# Oscar_s_schematic.net
KiCad netlist of a schematic drawn in EAGLE
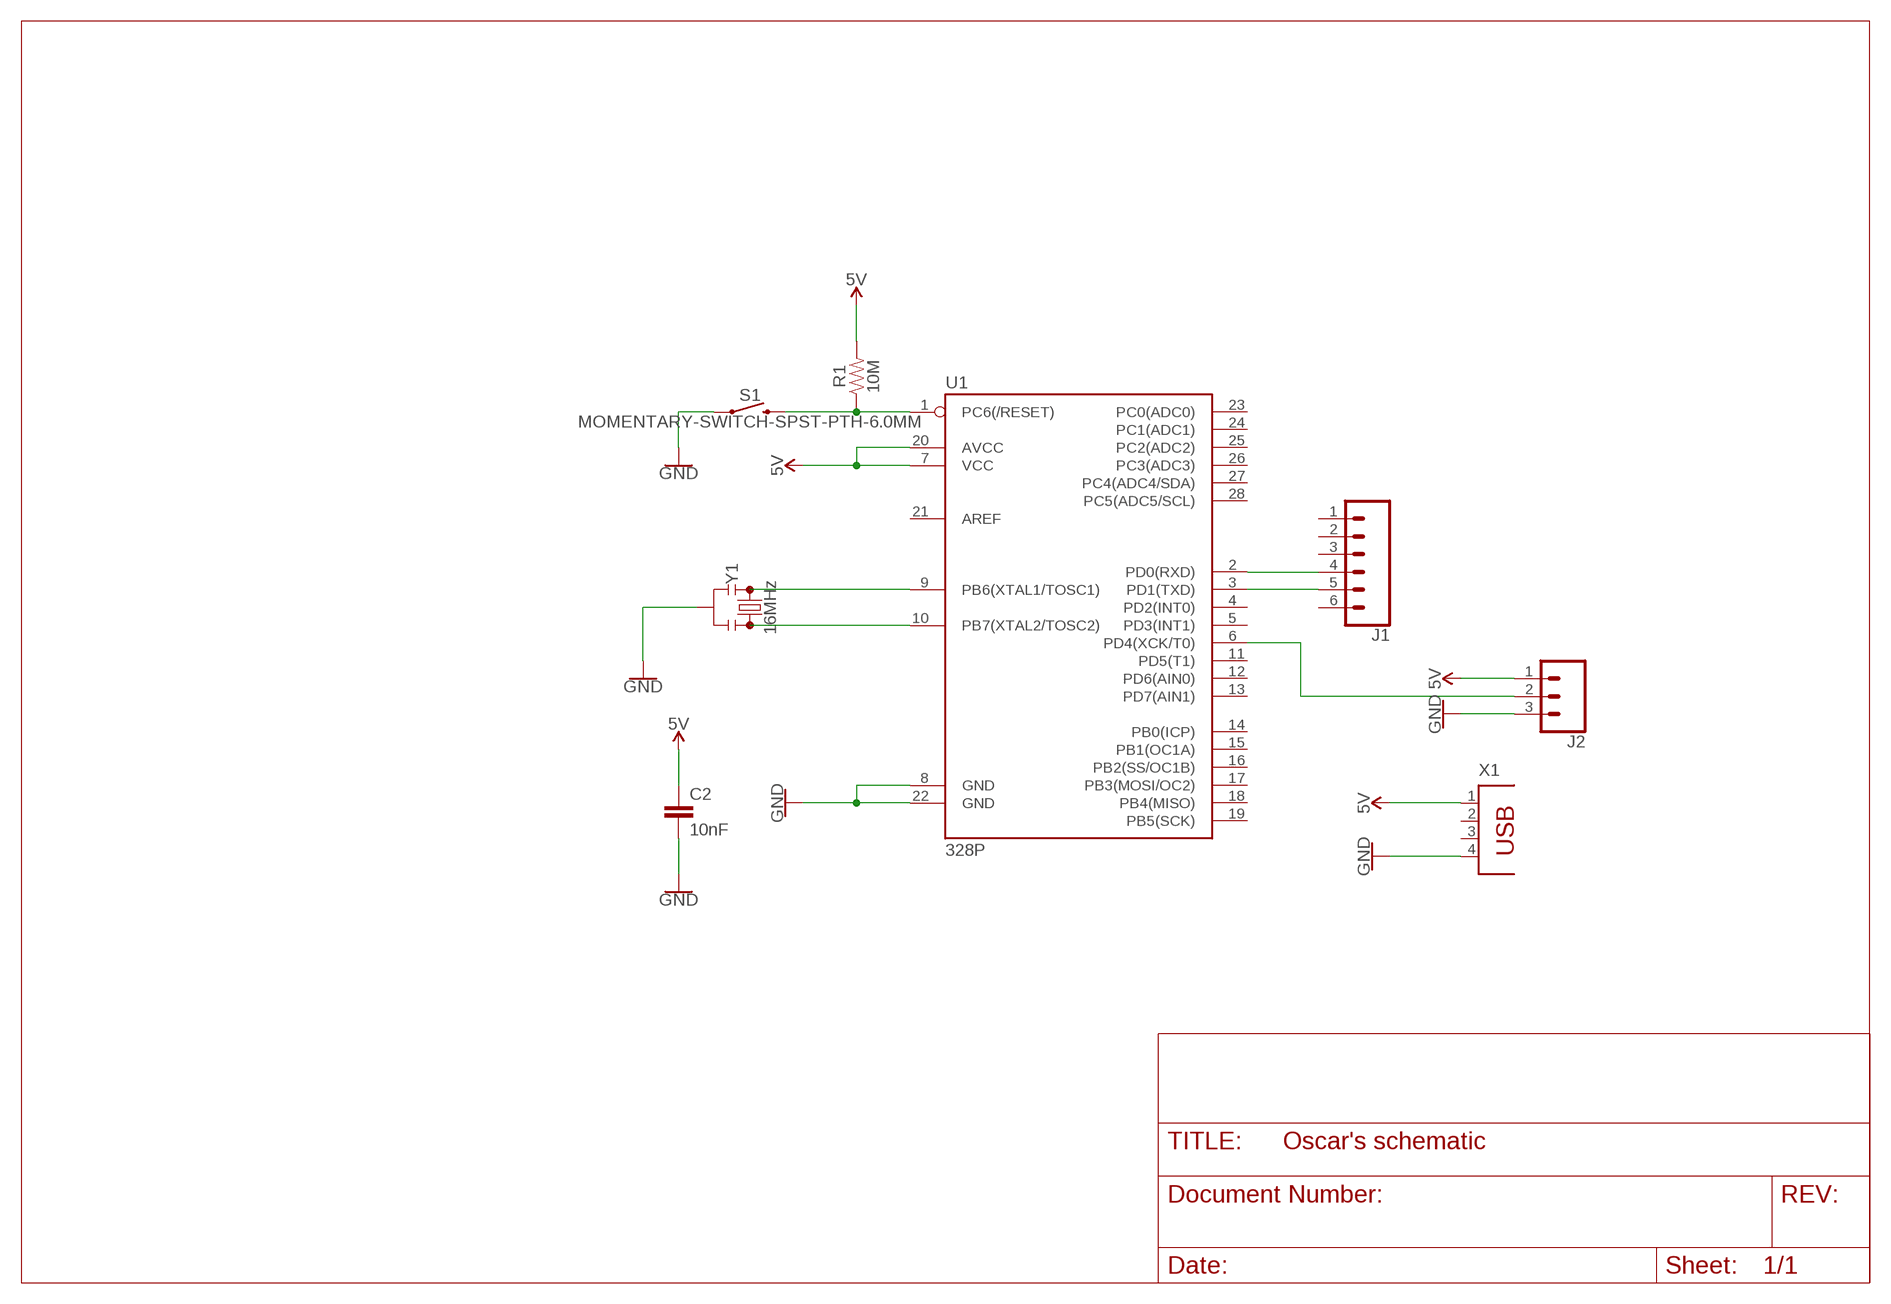
[diagram p0: schematic, sheet 1]

(export (version "E")
  (design (tool "Eeschema 10.0.6"))
  (components
    (comp (ref "C2")
      (value "10nF")
      (footprint "eagle-import:CAP-PTH-10MM")
      (libsource (lib "eagle-import") (part "10NF-PTH-10MM-10000V-1-%"))
    )
    (comp (ref "J1")
      (value "CONN_06LOCK")
      (footprint "eagle-import:1X06_LOCK")
      (libsource (lib "eagle-import") (part "CONN_06LOCK"))
    )
    (comp (ref "J2")
      (value "CONN_03")
      (footprint "eagle-import:1X03")
      (libsource (lib "eagle-import") (part "CONN_03"))
    )
    (comp (ref "R1")
      (value "10M")
      (footprint "eagle-import:AXIAL-0.3")
      (libsource (lib "eagle-import") (part "10MOHM-HORIZ-1/4W-5%"))
    )
    (comp (ref "S1")
      (value "MOMENTARY-SWITCH-SPST-PTH-6.0MM")
      (footprint "eagle-import:TACTILE_SWITCH_PTH_6.0MM")
      (libsource (lib "eagle-import") (part "MOMENTARY-SWITCH-SPST-PTH-6.0MM"))
    )
    (comp (ref "U1")
      (value "328P")
      (footprint "eagle-import:DIP28")
      (libsource (lib "eagle-import") (part "ATMEGA328P_PDIP"))
    )
    (comp (ref "X1")
      (value "PN61729")
      (footprint "eagle-import:PN61729")
      (libsource (lib "eagle-import") (part "PN61729"))
    )
    (comp (ref "Y1")
      (value "16MHz")
      (footprint "eagle-import:RESONATOR-SMD-3.2X1.3")
      (libsource (lib "eagle-import") (part "RESONATOR-16MHZSMD_3.2X1.3"))
    )
  )
  (nets
    (net (code "1") (name "5V") (class "Default")
      (node (ref "C2") (pin "1") (pinfunction "1_1") (pintype "passive"))
      (node (ref "J2") (pin "1") (pinfunction "1_1") (pintype "passive"))
      (node (ref "R1") (pin "P$2") (pinfunction "2_P$2") (pintype "passive"))
      (node (ref "U1") (pin "20") (pinfunction "AVCC_20") (pintype "bidirectional"))
      (node (ref "U1") (pin "7") (pinfunction "VCC_7") (pintype "bidirectional"))
      (node (ref "X1") (pin "1") (pinfunction "1_1") (pintype "passive"))
    )
    (net (code "2") (name "GND") (class "Default")
      (node (ref "C2") (pin "2") (pinfunction "2_2") (pintype "passive"))
      (node (ref "J2") (pin "3") (pinfunction "3_3") (pintype "passive"))
      (node (ref "S1") (pin "1") (pinfunction "1_1") (pintype "passive"))
      (node (ref "U1") (pin "22") (pinfunction "GND_22") (pintype "bidirectional"))
      (node (ref "U1") (pin "8") (pinfunction "GND_8") (pintype "bidirectional"))
      (node (ref "X1") (pin "4") (pinfunction "4_4") (pintype "passive"))
      (node (ref "Y1") (pin "2") (pinfunction "2_2") (pintype "passive"))
    )
    (net (code "3") (name "Net-(R1-1)") (class "Default")
      (node (ref "R1") (pin "P$1") (pinfunction "1_P$1") (pintype "passive"))
      (node (ref "S1") (pin "3") (pinfunction "2_3") (pintype "passive"))
      (node (ref "U1") (pin "1") (pinfunction "PC6(/RESET)_1") (pintype "bidirectional"))
    )
    (net (code "4") (name "Net-(U1-PB6(XTAL1{slash}TOSC1))") (class "Default")
      (node (ref "U1") (pin "9") (pinfunction "PB6(XTAL1/TOSC1)_9") (pintype "bidirectional"))
      (node (ref "Y1") (pin "1") (pinfunction "1_1") (pintype "passive"))
    )
    (net (code "5") (name "Net-(U1-PB7(XTAL2{slash}TOSC2))") (class "Default")
      (node (ref "U1") (pin "10") (pinfunction "PB7(XTAL2/TOSC2)_10") (pintype "bidirectional"))
      (node (ref "Y1") (pin "3") (pinfunction "3_3") (pintype "passive"))
    )
    (net (code "6") (name "Net-(U1-PD0(RXD))") (class "Default")
      (node (ref "J1") (pin "4") (pinfunction "4_4") (pintype "passive"))
      (node (ref "U1") (pin "2") (pinfunction "PD0(RXD)_2") (pintype "bidirectional"))
    )
    (net (code "7") (name "Net-(U1-PD1(TXD))") (class "Default")
      (node (ref "J1") (pin "5") (pinfunction "5_5") (pintype "passive"))
      (node (ref "U1") (pin "3") (pinfunction "PD1(TXD)_3") (pintype "bidirectional"))
    )
    (net (code "8") (name "Net-(U1-PD4(XCK{slash}T0))") (class "Default")
      (node (ref "J2") (pin "2") (pinfunction "2_2") (pintype "passive"))
      (node (ref "U1") (pin "6") (pinfunction "PD4(XCK/T0)_6") (pintype "bidirectional"))
    )
    (net (code "9") (name "unconnected-(J1-Pad1)") (class "Default")
      (node (ref "J1") (pin "1") (pinfunction "1_1") (pintype "passive"))
    )
    (net (code "10") (name "unconnected-(J1-Pad2)") (class "Default")
      (node (ref "J1") (pin "2") (pinfunction "2_2") (pintype "passive"))
    )
    (net (code "11") (name "unconnected-(J1-Pad3)") (class "Default")
      (node (ref "J1") (pin "3") (pinfunction "3_3") (pintype "passive"))
    )
    (net (code "12") (name "unconnected-(J1-Pad6)") (class "Default")
      (node (ref "J1") (pin "6") (pinfunction "6_6") (pintype "passive"))
    )
    (net (code "13") (name "unconnected-(U1-AREF-Pad21)") (class "Default")
      (node (ref "U1") (pin "21") (pinfunction "AREF_21") (pintype "bidirectional"))
    )
    (net (code "14") (name "unconnected-(U1-PB0(ICP)-Pad14)") (class "Default")
      (node (ref "U1") (pin "14") (pinfunction "PB0(ICP)_14") (pintype "bidirectional"))
    )
    (net (code "15") (name "unconnected-(U1-PB1(OC1A)-Pad15)") (class "Default")
      (node (ref "U1") (pin "15") (pinfunction "PB1(OC1A)_15") (pintype "bidirectional"))
    )
    (net (code "16") (name "unconnected-(U1-PB2(SS{slash}OC1B)-Pad16)") (class "Default")
      (node (ref "U1") (pin "16") (pinfunction "PB2(SS/OC1B)_16") (pintype "bidirectional"))
    )
    (net (code "17") (name "unconnected-(U1-PB3(MOSI{slash}OC2)-Pad17)") (class "Default")
      (node (ref "U1") (pin "17") (pinfunction "PB3(MOSI/OC2)_17") (pintype "bidirectional"))
    )
    (net (code "18") (name "unconnected-(U1-PB4(MISO)-Pad18)") (class "Default")
      (node (ref "U1") (pin "18") (pinfunction "PB4(MISO)_18") (pintype "bidirectional"))
    )
    (net (code "19") (name "unconnected-(U1-PB5(SCK)-Pad19)") (class "Default")
      (node (ref "U1") (pin "19") (pinfunction "PB5(SCK)_19") (pintype "bidirectional"))
    )
    (net (code "20") (name "unconnected-(U1-PC0(ADC0)-Pad23)") (class "Default")
      (node (ref "U1") (pin "23") (pinfunction "PC0(ADC0)_23") (pintype "bidirectional"))
    )
    (net (code "21") (name "unconnected-(U1-PC1(ADC1)-Pad24)") (class "Default")
      (node (ref "U1") (pin "24") (pinfunction "PC1(ADC1)_24") (pintype "bidirectional"))
    )
    (net (code "22") (name "unconnected-(U1-PC2(ADC2)-Pad25)") (class "Default")
      (node (ref "U1") (pin "25") (pinfunction "PC2(ADC2)_25") (pintype "bidirectional"))
    )
    (net (code "23") (name "unconnected-(U1-PC3(ADC3)-Pad26)") (class "Default")
      (node (ref "U1") (pin "26") (pinfunction "PC3(ADC3)_26") (pintype "bidirectional"))
    )
    (net (code "24") (name "unconnected-(U1-PC4(ADC4{slash}SDA)-Pad27)") (class "Default")
      (node (ref "U1") (pin "27") (pinfunction "PC4(ADC4/SDA)_27") (pintype "bidirectional"))
    )
    (net (code "25") (name "unconnected-(U1-PC5(ADC5{slash}SCL)-Pad28)") (class "Default")
      (node (ref "U1") (pin "28") (pinfunction "PC5(ADC5/SCL)_28") (pintype "bidirectional"))
    )
    (net (code "26") (name "unconnected-(U1-PD2(INT0)-Pad4)") (class "Default")
      (node (ref "U1") (pin "4") (pinfunction "PD2(INT0)_4") (pintype "bidirectional"))
    )
    (net (code "27") (name "unconnected-(U1-PD3(INT1)-Pad5)") (class "Default")
      (node (ref "U1") (pin "5") (pinfunction "PD3(INT1)_5") (pintype "bidirectional"))
    )
    (net (code "28") (name "unconnected-(U1-PD5(T1)-Pad11)") (class "Default")
      (node (ref "U1") (pin "11") (pinfunction "PD5(T1)_11") (pintype "bidirectional"))
    )
    (net (code "29") (name "unconnected-(U1-PD6(AIN0)-Pad12)") (class "Default")
      (node (ref "U1") (pin "12") (pinfunction "PD6(AIN0)_12") (pintype "bidirectional"))
    )
    (net (code "30") (name "unconnected-(U1-PD7(AIN1)-Pad13)") (class "Default")
      (node (ref "U1") (pin "13") (pinfunction "PD7(AIN1)_13") (pintype "bidirectional"))
    )
    (net (code "31") (name "unconnected-(X1-Pad2)") (class "Default")
      (node (ref "X1") (pin "2") (pinfunction "2_2") (pintype "passive"))
    )
    (net (code "32") (name "unconnected-(X1-Pad3)") (class "Default")
      (node (ref "X1") (pin "3") (pinfunction "3_3") (pintype "passive"))
    )
  )
)
